# Arduino-DUE-SHEILD.net
KiCad netlist of a schematic drawn in EAGLE
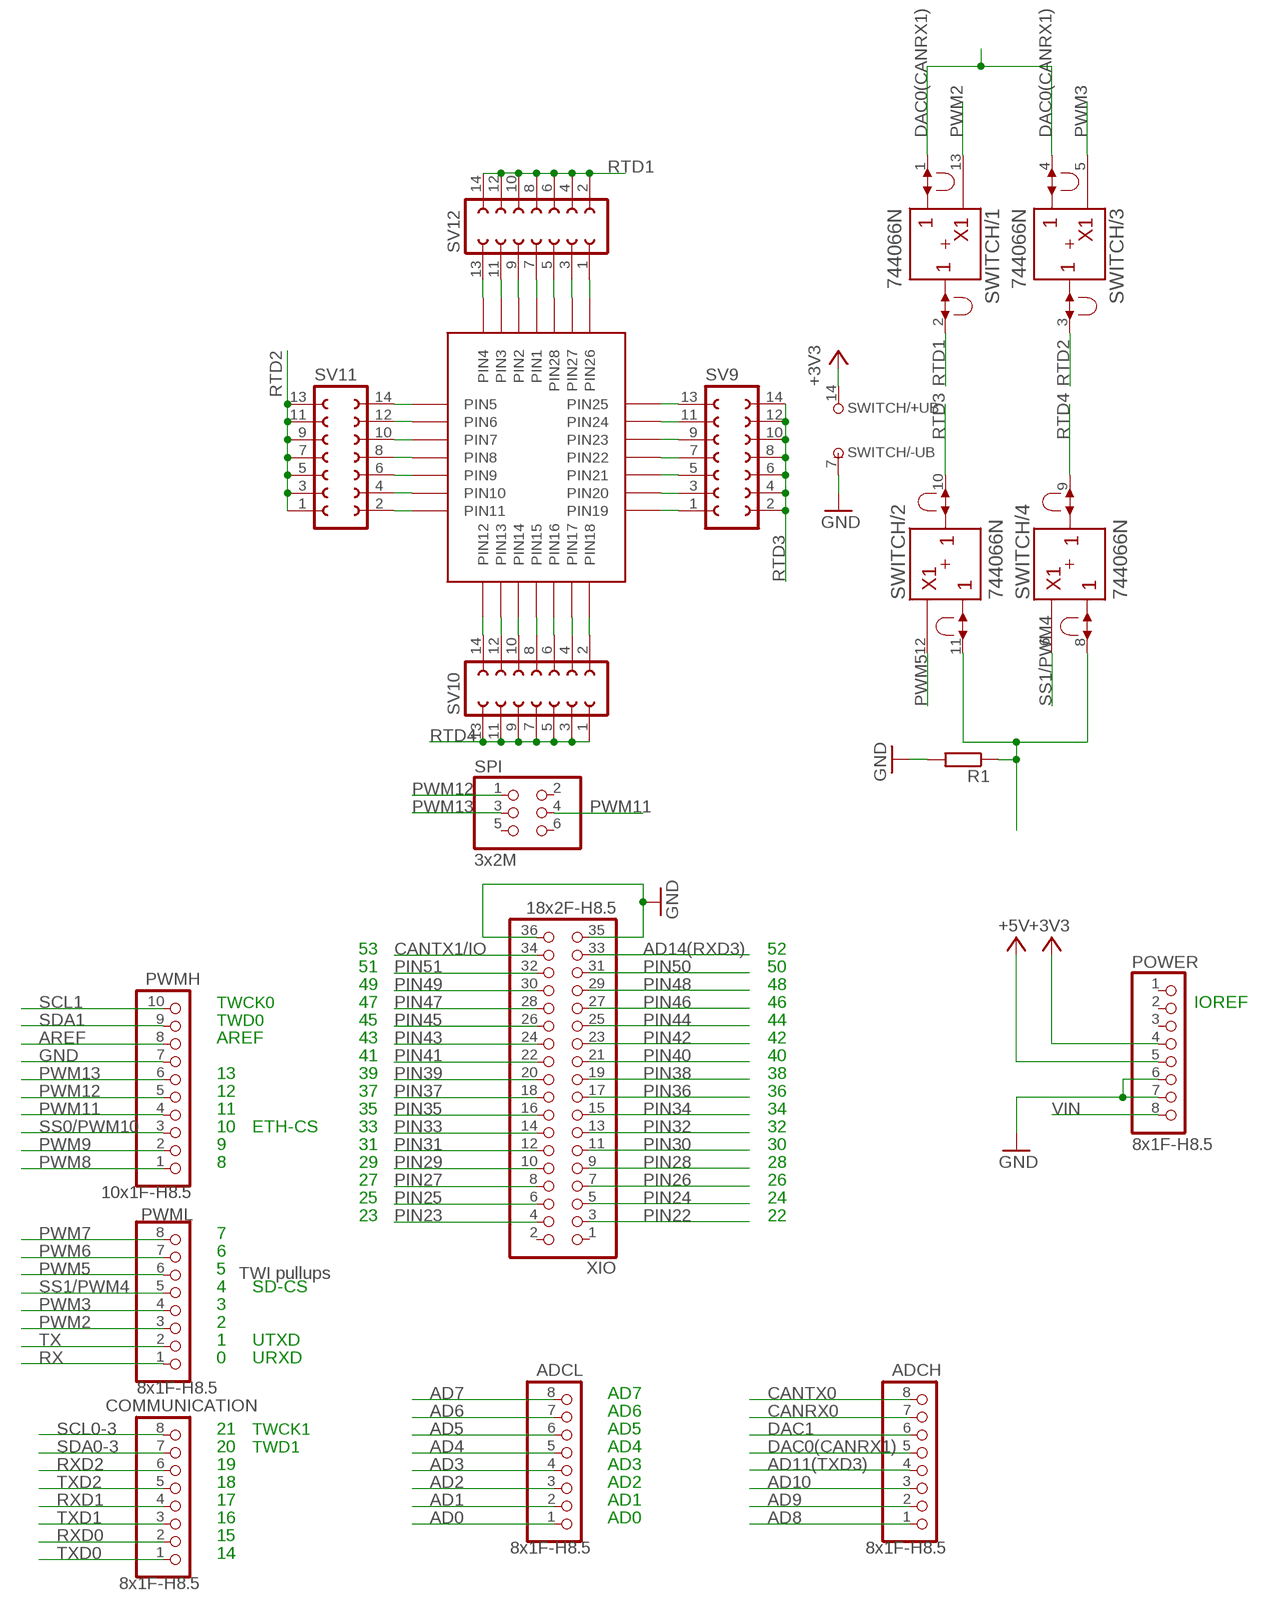
[diagram p0: schematic, sheet 1]

(export (version "E")
  (design (tool "Eeschema 10.0.6"))
  (components
    (comp (ref "ADCH")
      (value "8x1F-H8.5")
      (footprint "eagle-import:1X08")
      (libsource (lib "eagle-import") (part "PINHD-1X8"))
    )
    (comp (ref "ADCL")
      (value "8x1F-H8.5")
      (footprint "eagle-import:1X08")
      (libsource (lib "eagle-import") (part "PINHD-1X8"))
    )
    (comp (ref "COMMUNICATION")
      (value "8x1F-H8.5")
      (footprint "eagle-import:1X08")
      (libsource (lib "eagle-import") (part "PINHD-1X8"))
    )
    (comp (ref "POWER")
      (value "8x1F-H8.5")
      (footprint "eagle-import:1X08")
      (libsource (lib "eagle-import") (part "PINHD-1X8"))
    )
    (comp (ref "PWMH")
      (value "10x1F-H8.5")
      (footprint "eagle-import:1X10")
      (libsource (lib "eagle-import") (part "PINHD-1X10"))
    )
    (comp (ref "PWML")
      (value "8x1F-H8.5")
      (footprint "eagle-import:1X08")
      (libsource (lib "eagle-import") (part "PINHD-1X8"))
    )
    (comp (ref "R1")
      (value "R-EU_0207/7")
      (footprint "eagle-import:0207_7")
      (libsource (lib "eagle-import") (part "R-EU_0207/7"))
    )
    (comp (ref "SPI")
      (value "3x2M")
      (footprint "eagle-import:2X03")
      (libsource (lib "eagle-import") (part "PINHD-2X3"))
    )
    (comp (ref "SV9")
      (value "FE07-2")
      (footprint "eagle-import:FE07-2")
      (libsource (lib "eagle-import") (part "FE07-2"))
    )
    (comp (ref "SV10")
      (value "FE07-2")
      (footprint "eagle-import:FE07-2")
      (libsource (lib "eagle-import") (part "FE07-2"))
    )
    (comp (ref "SV11")
      (value "FE07-2")
      (footprint "eagle-import:FE07-2")
      (libsource (lib "eagle-import") (part "FE07-2"))
    )
    (comp (ref "SV12")
      (value "FE07-2")
      (footprint "eagle-import:FE07-2")
      (libsource (lib "eagle-import") (part "FE07-2"))
    )
    (comp (ref "SWITCH")
      (value "744066N")
      (footprint "eagle-import:DIL14")
      (libsource (lib "eagle-import") (part "744066N"))
    )
    (comp (ref "U$1")
      (value "S28")
      (footprint "eagle-import:S28")
      (libsource (lib "eagle-import") (part "S28"))
    )
    (comp (ref "XIO")
      (value "18x2F-H8.5")
      (footprint "eagle-import:2X18")
      (libsource (lib "eagle-import") (part "PINHD-2X18"))
    )
  )
  (nets
    (net (code "1") (name "+3V3") (class "Default")
      (node (ref "POWER") (pin "4") (pinfunction "4_4") (pintype "passive"))
      (node (ref "SWITCH") (pin "14") (pinfunction "+UB_14") (pintype "power_in"))
    )
    (net (code "2") (name "+5V") (class "Default")
      (node (ref "POWER") (pin "5") (pinfunction "5_5") (pintype "passive"))
    )
    (net (code "3") (name "/AD0") (class "Default")
      (node (ref "ADCL") (pin "1") (pinfunction "1_1") (pintype "passive"))
    )
    (net (code "4") (name "/AD1") (class "Default")
      (node (ref "ADCL") (pin "2") (pinfunction "2_2") (pintype "passive"))
    )
    (net (code "5") (name "/AD2") (class "Default")
      (node (ref "ADCL") (pin "3") (pinfunction "3_3") (pintype "passive"))
    )
    (net (code "6") (name "/AD3") (class "Default")
      (node (ref "ADCL") (pin "4") (pinfunction "4_4") (pintype "passive"))
    )
    (net (code "7") (name "/AD4") (class "Default")
      (node (ref "ADCL") (pin "5") (pinfunction "5_5") (pintype "passive"))
    )
    (net (code "8") (name "/AD5") (class "Default")
      (node (ref "ADCL") (pin "6") (pinfunction "6_6") (pintype "passive"))
      (node (ref "R1") (pin "1") (pinfunction "1_1") (pintype "passive"))
      (node (ref "SWITCH") (pin "11") (pinfunction "A_11") (pintype "passive"))
      (node (ref "SWITCH") (pin "8") (pinfunction "A_8") (pintype "passive"))
    )
    (net (code "9") (name "/AD6") (class "Default")
      (node (ref "ADCL") (pin "7") (pinfunction "7_7") (pintype "passive"))
    )
    (net (code "10") (name "/AD7") (class "Default")
      (node (ref "ADCL") (pin "8") (pinfunction "8_8") (pintype "passive"))
    )
    (net (code "11") (name "/AD8") (class "Default")
      (node (ref "ADCH") (pin "1") (pinfunction "1_1") (pintype "passive"))
    )
    (net (code "12") (name "/AD9") (class "Default")
      (node (ref "ADCH") (pin "2") (pinfunction "2_2") (pintype "passive"))
    )
    (net (code "13") (name "/AD10") (class "Default")
      (node (ref "ADCH") (pin "3") (pinfunction "3_3") (pintype "passive"))
    )
    (net (code "14") (name "/AD11(TXD3)") (class "Default")
      (node (ref "ADCH") (pin "4") (pinfunction "4_4") (pintype "passive"))
    )
    (net (code "15") (name "/AD14(RXD3)") (class "Default")
      (node (ref "XIO") (pin "33") (pinfunction "33_33") (pintype "passive"))
    )
    (net (code "16") (name "/AREF") (class "Default")
      (node (ref "PWMH") (pin "8") (pinfunction "8_8") (pintype "passive"))
    )
    (net (code "17") (name "/CANRX0") (class "Default")
      (node (ref "ADCH") (pin "7") (pinfunction "7_7") (pintype "passive"))
    )
    (net (code "18") (name "/CANTX0") (class "Default")
      (node (ref "ADCH") (pin "8") (pinfunction "8_8") (pintype "passive"))
    )
    (net (code "19") (name "/CANTX1{slash}IO") (class "Default")
      (node (ref "XIO") (pin "34") (pinfunction "34_34") (pintype "passive"))
    )
    (net (code "20") (name "/DAC0(CANRX1)") (class "Default")
      (node (ref "ADCH") (pin "5") (pinfunction "5_5") (pintype "passive"))
      (node (ref "SWITCH") (pin "1") (pinfunction "A_1") (pintype "passive"))
      (node (ref "SWITCH") (pin "4") (pinfunction "A_4") (pintype "passive"))
    )
    (net (code "21") (name "/DAC1") (class "Default")
      (node (ref "ADCH") (pin "6") (pinfunction "6_6") (pintype "passive"))
    )
    (net (code "22") (name "/PIN22") (class "Default")
      (node (ref "XIO") (pin "3") (pinfunction "3_3") (pintype "passive"))
    )
    (net (code "23") (name "/PIN23") (class "Default")
      (node (ref "XIO") (pin "4") (pinfunction "4_4") (pintype "passive"))
    )
    (net (code "24") (name "/PIN24") (class "Default")
      (node (ref "XIO") (pin "5") (pinfunction "5_5") (pintype "passive"))
    )
    (net (code "25") (name "/PIN25") (class "Default")
      (node (ref "XIO") (pin "6") (pinfunction "6_6") (pintype "passive"))
    )
    (net (code "26") (name "/PIN26") (class "Default")
      (node (ref "XIO") (pin "7") (pinfunction "7_7") (pintype "passive"))
    )
    (net (code "27") (name "/PIN27") (class "Default")
      (node (ref "XIO") (pin "8") (pinfunction "8_8") (pintype "passive"))
    )
    (net (code "28") (name "/PIN28") (class "Default")
      (node (ref "XIO") (pin "9") (pinfunction "9_9") (pintype "passive"))
    )
    (net (code "29") (name "/PIN29") (class "Default")
      (node (ref "XIO") (pin "10") (pinfunction "10_10") (pintype "passive"))
    )
    (net (code "30") (name "/PIN30") (class "Default")
      (node (ref "XIO") (pin "11") (pinfunction "11_11") (pintype "passive"))
    )
    (net (code "31") (name "/PIN31") (class "Default")
      (node (ref "XIO") (pin "12") (pinfunction "12_12") (pintype "passive"))
    )
    (net (code "32") (name "/PIN32") (class "Default")
      (node (ref "XIO") (pin "13") (pinfunction "13_13") (pintype "passive"))
    )
    (net (code "33") (name "/PIN33") (class "Default")
      (node (ref "XIO") (pin "14") (pinfunction "14_14") (pintype "passive"))
    )
    (net (code "34") (name "/PIN34") (class "Default")
      (node (ref "XIO") (pin "15") (pinfunction "15_15") (pintype "passive"))
    )
    (net (code "35") (name "/PIN35") (class "Default")
      (node (ref "XIO") (pin "16") (pinfunction "16_16") (pintype "passive"))
    )
    (net (code "36") (name "/PIN36") (class "Default")
      (node (ref "XIO") (pin "17") (pinfunction "17_17") (pintype "passive"))
    )
    (net (code "37") (name "/PIN37") (class "Default")
      (node (ref "XIO") (pin "18") (pinfunction "18_18") (pintype "passive"))
    )
    (net (code "38") (name "/PIN38") (class "Default")
      (node (ref "XIO") (pin "19") (pinfunction "19_19") (pintype "passive"))
    )
    (net (code "39") (name "/PIN39") (class "Default")
      (node (ref "XIO") (pin "20") (pinfunction "20_20") (pintype "passive"))
    )
    (net (code "40") (name "/PIN40") (class "Default")
      (node (ref "XIO") (pin "21") (pinfunction "21_21") (pintype "passive"))
    )
    (net (code "41") (name "/PIN41") (class "Default")
      (node (ref "XIO") (pin "22") (pinfunction "22_22") (pintype "passive"))
    )
    (net (code "42") (name "/PIN42") (class "Default")
      (node (ref "XIO") (pin "23") (pinfunction "23_23") (pintype "passive"))
    )
    (net (code "43") (name "/PIN43") (class "Default")
      (node (ref "XIO") (pin "24") (pinfunction "24_24") (pintype "passive"))
    )
    (net (code "44") (name "/PIN44") (class "Default")
      (node (ref "XIO") (pin "25") (pinfunction "25_25") (pintype "passive"))
    )
    (net (code "45") (name "/PIN45") (class "Default")
      (node (ref "XIO") (pin "26") (pinfunction "26_26") (pintype "passive"))
    )
    (net (code "46") (name "/PIN46") (class "Default")
      (node (ref "XIO") (pin "27") (pinfunction "27_27") (pintype "passive"))
    )
    (net (code "47") (name "/PIN47") (class "Default")
      (node (ref "XIO") (pin "28") (pinfunction "28_28") (pintype "passive"))
    )
    (net (code "48") (name "/PIN48") (class "Default")
      (node (ref "XIO") (pin "29") (pinfunction "29_29") (pintype "passive"))
    )
    (net (code "49") (name "/PIN49") (class "Default")
      (node (ref "XIO") (pin "30") (pinfunction "30_30") (pintype "passive"))
    )
    (net (code "50") (name "/PIN50") (class "Default")
      (node (ref "XIO") (pin "31") (pinfunction "31_31") (pintype "passive"))
    )
    (net (code "51") (name "/PIN51") (class "Default")
      (node (ref "XIO") (pin "32") (pinfunction "32_32") (pintype "passive"))
    )
    (net (code "52") (name "/PWM2") (class "Default")
      (node (ref "PWML") (pin "3") (pinfunction "3_3") (pintype "passive"))
      (node (ref "SWITCH") (pin "13") (pinfunction "C_13") (pintype "input"))
    )
    (net (code "53") (name "/PWM3") (class "Default")
      (node (ref "PWML") (pin "4") (pinfunction "4_4") (pintype "passive"))
      (node (ref "SWITCH") (pin "5") (pinfunction "C_5") (pintype "input"))
    )
    (net (code "54") (name "/PWM5") (class "Default")
      (node (ref "PWML") (pin "6") (pinfunction "6_6") (pintype "passive"))
      (node (ref "SWITCH") (pin "12") (pinfunction "C_12") (pintype "input"))
    )
    (net (code "55") (name "/PWM6") (class "Default")
      (node (ref "PWML") (pin "7") (pinfunction "7_7") (pintype "passive"))
    )
    (net (code "56") (name "/PWM7") (class "Default")
      (node (ref "PWML") (pin "8") (pinfunction "8_8") (pintype "passive"))
    )
    (net (code "57") (name "/PWM8") (class "Default")
      (node (ref "PWMH") (pin "1") (pinfunction "1_1") (pintype "passive"))
    )
    (net (code "58") (name "/PWM9") (class "Default")
      (node (ref "PWMH") (pin "2") (pinfunction "2_2") (pintype "passive"))
    )
    (net (code "59") (name "/PWM11") (class "Default")
      (node (ref "PWMH") (pin "4") (pinfunction "4_4") (pintype "passive"))
      (node (ref "SPI") (pin "4") (pinfunction "4_4") (pintype "passive"))
    )
    (net (code "60") (name "/PWM12") (class "Default")
      (node (ref "PWMH") (pin "5") (pinfunction "5_5") (pintype "passive"))
      (node (ref "SPI") (pin "1") (pinfunction "1_1") (pintype "passive"))
    )
    (net (code "61") (name "/PWM13") (class "Default")
      (node (ref "PWMH") (pin "6") (pinfunction "6_6") (pintype "passive"))
      (node (ref "SPI") (pin "3") (pinfunction "3_3") (pintype "passive"))
    )
    (net (code "62") (name "/RTD1") (class "Default")
      (node (ref "SV12") (pin "10") (pinfunction "10_10") (pintype "passive"))
      (node (ref "SV12") (pin "12") (pinfunction "12_12") (pintype "passive"))
      (node (ref "SV12") (pin "14") (pinfunction "14_14") (pintype "passive"))
      (node (ref "SV12") (pin "2") (pinfunction "2_2") (pintype "passive"))
      (node (ref "SV12") (pin "4") (pinfunction "4_4") (pintype "passive"))
      (node (ref "SV12") (pin "6") (pinfunction "6_6") (pintype "passive"))
      (node (ref "SV12") (pin "8") (pinfunction "8_8") (pintype "passive"))
      (node (ref "SWITCH") (pin "2") (pinfunction "B_2") (pintype "passive"))
    )
    (net (code "63") (name "/RTD2") (class "Default")
      (node (ref "SV11") (pin "1") (pinfunction "1_1") (pintype "passive"))
      (node (ref "SV11") (pin "11") (pinfunction "11_11") (pintype "passive"))
      (node (ref "SV11") (pin "13") (pinfunction "13_13") (pintype "passive"))
      (node (ref "SV11") (pin "3") (pinfunction "3_3") (pintype "passive"))
      (node (ref "SV11") (pin "5") (pinfunction "5_5") (pintype "passive"))
      (node (ref "SV11") (pin "7") (pinfunction "7_7") (pintype "passive"))
      (node (ref "SV11") (pin "9") (pinfunction "9_9") (pintype "passive"))
      (node (ref "SWITCH") (pin "3") (pinfunction "B_3") (pintype "passive"))
    )
    (net (code "64") (name "/RTD3") (class "Default")
      (node (ref "SV9") (pin "10") (pinfunction "10_10") (pintype "passive"))
      (node (ref "SV9") (pin "12") (pinfunction "12_12") (pintype "passive"))
      (node (ref "SV9") (pin "14") (pinfunction "14_14") (pintype "passive"))
      (node (ref "SV9") (pin "2") (pinfunction "2_2") (pintype "passive"))
      (node (ref "SV9") (pin "4") (pinfunction "4_4") (pintype "passive"))
      (node (ref "SV9") (pin "6") (pinfunction "6_6") (pintype "passive"))
      (node (ref "SV9") (pin "8") (pinfunction "8_8") (pintype "passive"))
      (node (ref "SWITCH") (pin "10") (pinfunction "B_10") (pintype "passive"))
    )
    (net (code "65") (name "/RTD4") (class "Default")
      (node (ref "SV10") (pin "1") (pinfunction "1_1") (pintype "passive"))
      (node (ref "SV10") (pin "11") (pinfunction "11_11") (pintype "passive"))
      (node (ref "SV10") (pin "13") (pinfunction "13_13") (pintype "passive"))
      (node (ref "SV10") (pin "3") (pinfunction "3_3") (pintype "passive"))
      (node (ref "SV10") (pin "5") (pinfunction "5_5") (pintype "passive"))
      (node (ref "SV10") (pin "7") (pinfunction "7_7") (pintype "passive"))
      (node (ref "SV10") (pin "9") (pinfunction "9_9") (pintype "passive"))
      (node (ref "SWITCH") (pin "9") (pinfunction "B_9") (pintype "passive"))
    )
    (net (code "66") (name "/RX") (class "Default")
      (node (ref "PWML") (pin "1") (pinfunction "1_1") (pintype "passive"))
    )
    (net (code "67") (name "/RXD0") (class "Default")
      (node (ref "COMMUNICATION") (pin "2") (pinfunction "2_2") (pintype "passive"))
    )
    (net (code "68") (name "/RXD1") (class "Default")
      (node (ref "COMMUNICATION") (pin "4") (pinfunction "4_4") (pintype "passive"))
    )
    (net (code "69") (name "/RXD2") (class "Default")
      (node (ref "COMMUNICATION") (pin "6") (pinfunction "6_6") (pintype "passive"))
    )
    (net (code "70") (name "/SCL0-3") (class "Default")
      (node (ref "COMMUNICATION") (pin "8") (pinfunction "8_8") (pintype "passive"))
    )
    (net (code "71") (name "/SCL1") (class "Default")
      (node (ref "PWMH") (pin "10") (pinfunction "10_10") (pintype "passive"))
    )
    (net (code "72") (name "/SDA0-3") (class "Default")
      (node (ref "COMMUNICATION") (pin "7") (pinfunction "7_7") (pintype "passive"))
    )
    (net (code "73") (name "/SDA1") (class "Default")
      (node (ref "PWMH") (pin "9") (pinfunction "9_9") (pintype "passive"))
    )
    (net (code "74") (name "/SS0{slash}PWM10") (class "Default")
      (node (ref "PWMH") (pin "3") (pinfunction "3_3") (pintype "passive"))
    )
    (net (code "75") (name "/SS1{slash}PWM4") (class "Default")
      (node (ref "PWML") (pin "5") (pinfunction "5_5") (pintype "passive"))
      (node (ref "SWITCH") (pin "6") (pinfunction "C_6") (pintype "input"))
    )
    (net (code "76") (name "/TX") (class "Default")
      (node (ref "PWML") (pin "2") (pinfunction "2_2") (pintype "passive"))
    )
    (net (code "77") (name "/TXD0") (class "Default")
      (node (ref "COMMUNICATION") (pin "1") (pinfunction "1_1") (pintype "passive"))
    )
    (net (code "78") (name "/TXD1") (class "Default")
      (node (ref "COMMUNICATION") (pin "3") (pinfunction "3_3") (pintype "passive"))
    )
    (net (code "79") (name "/TXD2") (class "Default")
      (node (ref "COMMUNICATION") (pin "5") (pinfunction "5_5") (pintype "passive"))
    )
    (net (code "80") (name "/VIN") (class "Default")
      (node (ref "POWER") (pin "8") (pinfunction "8_8") (pintype "passive"))
    )
    (net (code "81") (name "GND") (class "Default")
      (node (ref "POWER") (pin "6") (pinfunction "6_6") (pintype "passive"))
      (node (ref "POWER") (pin "7") (pinfunction "7_7") (pintype "passive"))
      (node (ref "PWMH") (pin "7") (pinfunction "7_7") (pintype "passive"))
      (node (ref "R1") (pin "2") (pinfunction "2_2") (pintype "passive"))
      (node (ref "SWITCH") (pin "7") (pinfunction "-UB_7") (pintype "power_in"))
      (node (ref "XIO") (pin "35") (pinfunction "35_35") (pintype "passive"))
      (node (ref "XIO") (pin "36") (pinfunction "36_36") (pintype "passive"))
    )
    (net (code "82") (name "Net-(U$1-PIN1)") (class "Default")
      (node (ref "SV12") (pin "7") (pinfunction "7_7") (pintype "passive"))
      (node (ref "U$1") (pin "1") (pinfunction "PIN1_1") (pintype "bidirectional"))
    )
    (net (code "83") (name "Net-(U$1-PIN2)") (class "Default")
      (node (ref "SV12") (pin "9") (pinfunction "9_9") (pintype "passive"))
      (node (ref "U$1") (pin "2") (pinfunction "PIN2_2") (pintype "bidirectional"))
    )
    (net (code "84") (name "Net-(U$1-PIN3)") (class "Default")
      (node (ref "SV12") (pin "11") (pinfunction "11_11") (pintype "passive"))
      (node (ref "U$1") (pin "3") (pinfunction "PIN3_3") (pintype "bidirectional"))
    )
    (net (code "85") (name "Net-(U$1-PIN4)") (class "Default")
      (node (ref "SV12") (pin "13") (pinfunction "13_13") (pintype "passive"))
      (node (ref "U$1") (pin "4") (pinfunction "PIN4_4") (pintype "bidirectional"))
    )
    (net (code "86") (name "Net-(U$1-PIN5)") (class "Default")
      (node (ref "SV11") (pin "14") (pinfunction "14_14") (pintype "passive"))
      (node (ref "U$1") (pin "5") (pinfunction "PIN5_5") (pintype "bidirectional"))
    )
    (net (code "87") (name "Net-(U$1-PIN6)") (class "Default")
      (node (ref "SV11") (pin "12") (pinfunction "12_12") (pintype "passive"))
      (node (ref "U$1") (pin "6") (pinfunction "PIN6_6") (pintype "bidirectional"))
    )
    (net (code "88") (name "Net-(U$1-PIN7)") (class "Default")
      (node (ref "SV11") (pin "10") (pinfunction "10_10") (pintype "passive"))
      (node (ref "U$1") (pin "7") (pinfunction "PIN7_7") (pintype "bidirectional"))
    )
    (net (code "89") (name "Net-(U$1-PIN8)") (class "Default")
      (node (ref "SV11") (pin "8") (pinfunction "8_8") (pintype "passive"))
      (node (ref "U$1") (pin "8") (pinfunction "PIN8_8") (pintype "bidirectional"))
    )
    (net (code "90") (name "Net-(U$1-PIN9)") (class "Default")
      (node (ref "SV11") (pin "6") (pinfunction "6_6") (pintype "passive"))
      (node (ref "U$1") (pin "9") (pinfunction "PIN9_9") (pintype "bidirectional"))
    )
    (net (code "91") (name "Net-(U$1-PIN10)") (class "Default")
      (node (ref "SV11") (pin "4") (pinfunction "4_4") (pintype "passive"))
      (node (ref "U$1") (pin "10") (pinfunction "PIN10_10") (pintype "bidirectional"))
    )
    (net (code "92") (name "Net-(U$1-PIN11)") (class "Default")
      (node (ref "SV11") (pin "2") (pinfunction "2_2") (pintype "passive"))
      (node (ref "U$1") (pin "11") (pinfunction "PIN11_11") (pintype "bidirectional"))
    )
    (net (code "93") (name "Net-(U$1-PIN12)") (class "Default")
      (node (ref "SV10") (pin "14") (pinfunction "14_14") (pintype "passive"))
      (node (ref "U$1") (pin "12") (pinfunction "PIN12_12") (pintype "bidirectional"))
    )
    (net (code "94") (name "Net-(U$1-PIN13)") (class "Default")
      (node (ref "SV10") (pin "12") (pinfunction "12_12") (pintype "passive"))
      (node (ref "U$1") (pin "13") (pinfunction "PIN13_13") (pintype "bidirectional"))
    )
    (net (code "95") (name "Net-(U$1-PIN14)") (class "Default")
      (node (ref "SV10") (pin "10") (pinfunction "10_10") (pintype "passive"))
      (node (ref "U$1") (pin "14") (pinfunction "PIN14_14") (pintype "bidirectional"))
    )
    (net (code "96") (name "Net-(U$1-PIN15)") (class "Default")
      (node (ref "SV10") (pin "8") (pinfunction "8_8") (pintype "passive"))
      (node (ref "U$1") (pin "15") (pinfunction "PIN15_15") (pintype "bidirectional"))
    )
    (net (code "97") (name "Net-(U$1-PIN16)") (class "Default")
      (node (ref "SV10") (pin "6") (pinfunction "6_6") (pintype "passive"))
      (node (ref "U$1") (pin "16") (pinfunction "PIN16_16") (pintype "bidirectional"))
    )
    (net (code "98") (name "Net-(U$1-PIN17)") (class "Default")
      (node (ref "SV10") (pin "4") (pinfunction "4_4") (pintype "passive"))
      (node (ref "U$1") (pin "17") (pinfunction "PIN17_17") (pintype "bidirectional"))
    )
    (net (code "99") (name "Net-(U$1-PIN18)") (class "Default")
      (node (ref "SV10") (pin "2") (pinfunction "2_2") (pintype "passive"))
      (node (ref "U$1") (pin "18") (pinfunction "PIN18_18") (pintype "bidirectional"))
    )
    (net (code "100") (name "Net-(U$1-PIN19)") (class "Default")
      (node (ref "SV9") (pin "1") (pinfunction "1_1") (pintype "passive"))
      (node (ref "U$1") (pin "19") (pinfunction "PIN19_19") (pintype "bidirectional"))
    )
    (net (code "101") (name "Net-(U$1-PIN20)") (class "Default")
      (node (ref "SV9") (pin "3") (pinfunction "3_3") (pintype "passive"))
      (node (ref "U$1") (pin "20") (pinfunction "PIN20_20") (pintype "bidirectional"))
    )
    (net (code "102") (name "Net-(U$1-PIN21)") (class "Default")
      (node (ref "SV9") (pin "5") (pinfunction "5_5") (pintype "passive"))
      (node (ref "U$1") (pin "21") (pinfunction "PIN21_21") (pintype "bidirectional"))
    )
    (net (code "103") (name "Net-(U$1-PIN22)") (class "Default")
      (node (ref "SV9") (pin "7") (pinfunction "7_7") (pintype "passive"))
      (node (ref "U$1") (pin "22") (pinfunction "PIN22_22") (pintype "bidirectional"))
    )
    (net (code "104") (name "Net-(U$1-PIN23)") (class "Default")
      (node (ref "SV9") (pin "9") (pinfunction "9_9") (pintype "passive"))
      (node (ref "U$1") (pin "23") (pinfunction "PIN23_23") (pintype "bidirectional"))
    )
    (net (code "105") (name "Net-(U$1-PIN24)") (class "Default")
      (node (ref "SV9") (pin "11") (pinfunction "11_11") (pintype "passive"))
      (node (ref "U$1") (pin "24") (pinfunction "PIN24_24") (pintype "bidirectional"))
    )
    (net (code "106") (name "Net-(U$1-PIN25)") (class "Default")
      (node (ref "SV9") (pin "13") (pinfunction "13_13") (pintype "passive"))
      (node (ref "U$1") (pin "25") (pinfunction "PIN25_25") (pintype "bidirectional"))
    )
    (net (code "107") (name "Net-(U$1-PIN26)") (class "Default")
      (node (ref "SV12") (pin "1") (pinfunction "1_1") (pintype "passive"))
      (node (ref "U$1") (pin "26") (pinfunction "PIN26_26") (pintype "bidirectional"))
    )
    (net (code "108") (name "Net-(U$1-PIN27)") (class "Default")
      (node (ref "SV12") (pin "3") (pinfunction "3_3") (pintype "passive"))
      (node (ref "U$1") (pin "27") (pinfunction "PIN27_27") (pintype "bidirectional"))
    )
    (net (code "109") (name "Net-(U$1-PIN28)") (class "Default")
      (node (ref "SV12") (pin "5") (pinfunction "5_5") (pintype "passive"))
      (node (ref "U$1") (pin "28") (pinfunction "PIN28_28") (pintype "bidirectional"))
    )
    (net (code "110") (name "unconnected-(POWER-Pad1)") (class "Default")
      (node (ref "POWER") (pin "1") (pinfunction "1_1") (pintype "passive"))
    )
    (net (code "111") (name "unconnected-(POWER-Pad2)") (class "Default")
      (node (ref "POWER") (pin "2") (pinfunction "2_2") (pintype "passive"))
    )
    (net (code "112") (name "unconnected-(POWER-Pad3)") (class "Default")
      (node (ref "POWER") (pin "3") (pinfunction "3_3") (pintype "passive"))
    )
    (net (code "113") (name "unconnected-(SPI-Pad2)") (class "Default")
      (node (ref "SPI") (pin "2") (pinfunction "2_2") (pintype "passive"))
    )
    (net (code "114") (name "unconnected-(SPI-Pad5)") (class "Default")
      (node (ref "SPI") (pin "5") (pinfunction "5_5") (pintype "passive"))
    )
    (net (code "115") (name "unconnected-(SPI-Pad6)") (class "Default")
      (node (ref "SPI") (pin "6") (pinfunction "6_6") (pintype "passive"))
    )
    (net (code "116") (name "unconnected-(XIO-Pad1)") (class "Default")
      (node (ref "XIO") (pin "1") (pinfunction "1_1") (pintype "passive"))
    )
    (net (code "117") (name "unconnected-(XIO-Pad2)") (class "Default")
      (node (ref "XIO") (pin "2") (pinfunction "2_2") (pintype "passive"))
    )
  )
)
